# Analog-System.net
KiCad netlist of a schematic drawn in EAGLE
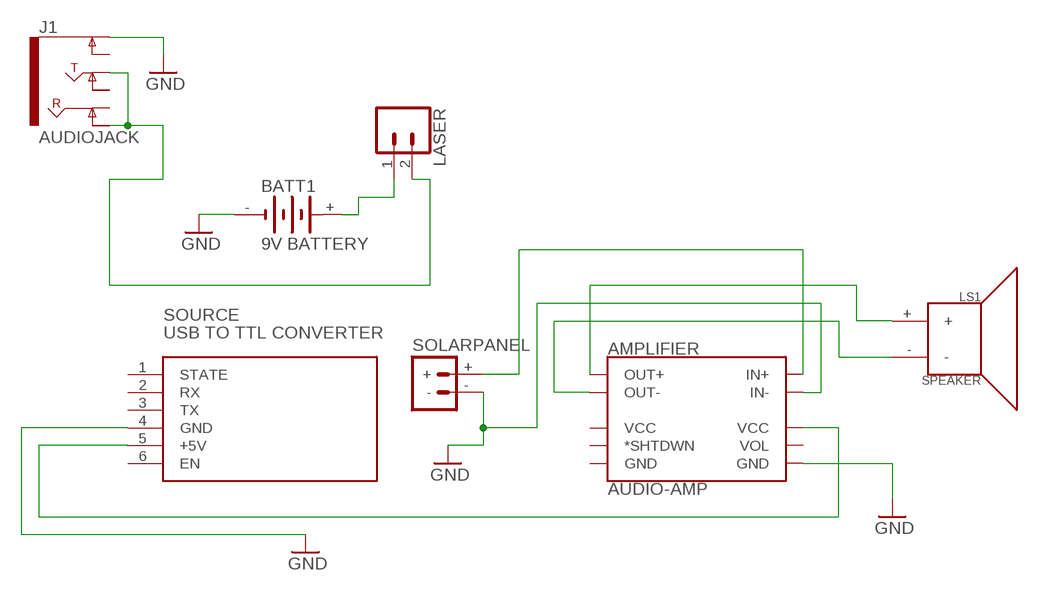
[diagram p0: schematic, sheet 1]

(export (version "E")
  (design (tool "Eeschema 10.0.6"))
  (components
    (comp (ref "AMPLIFIER")
      (value "AUDIO-AMP")
      (footprint "eagle-import:AUDIO-AMP-MONO")
      (libsource (lib "eagle-import") (part "SPARKFUN_AUDIO-AMP-MONODIP"))
    )
    (comp (ref "BATT1")
      (value "9V BATTERY")
      (footprint "eagle-import:2464BATT_HOLDER")
      (libsource (lib "eagle-import") (part "2464_BATT_HOLDER"))
    )
    (comp (ref "J1")
      (value "AUDIOJACK")
      (footprint "eagle-import:AUDIO_JACK_0.25__TRS_PTH_RA")
      (libsource (lib "eagle-import") (part "AUDIO_JACK_TRS_0.25{dblquote}_PTH_RA"))
    )
    (comp (ref "LASER")
      (value "CONN_02")
      (footprint "eagle-import:1X02")
      (libsource (lib "eagle-import") (part "CONN_02"))
    )
    (comp (ref "LS1")
      (value "SPEAKER")
      (footprint "eagle-import:PCB_MOUNT_SPEAKER")
      (libsource (lib "eagle-import") (part "SPEAKER"))
    )
    (comp (ref "SOLARPANEL")
      (value "BATTERY_CONN_DEANS")
      (footprint "eagle-import:DEANS")
      (libsource (lib "eagle-import") (part "BATTERY_CONN_DEANS"))
    )
    (comp (ref "SOURCE")
      (value "USB TO TTL CONVERTER")
      (footprint "eagle-import:WIRELESS-BLUETOOTH-HC-05")
      (libsource (lib "eagle-import") (part "WIRELESS-BLUETOOTH-HC-05"))
    )
  )
  (nets
    (net (code "1") (name "GND") (class "Default")
      (node (ref "AMPLIFIER") (pin "IN-") (pinfunction "IN-_IN-") (pintype "bidirectional"))
      (node (ref "AMPLIFIER") (pin "VOL-") (pinfunction "GND_VOL-") (pintype "bidirectional"))
      (node (ref "BATT1") (pin "-") (pinfunction "-_-") (pintype "passive"))
      (node (ref "J1") (pin "SLEEVE") (pinfunction "EARTH_SLEEVE") (pintype "bidirectional"))
      (node (ref "SOLARPANEL") (pin "-") (pinfunction "-_-") (pintype "passive"))
      (node (ref "SOURCE") (pin "4") (pinfunction "GND_4") (pintype "power_in"))
    )
    (net (code "2") (name "Net-(AMPLIFIER-PadIN+)") (class "Default")
      (node (ref "AMPLIFIER") (pin "IN+") (pinfunction "IN+_IN+") (pintype "bidirectional"))
      (node (ref "SOLARPANEL") (pin "+") (pinfunction "+_+") (pintype "passive"))
    )
    (net (code "3") (name "Net-(AMPLIFIER-PadOUT+)") (class "Default")
      (node (ref "AMPLIFIER") (pin "OUT+") (pinfunction "OUT+_OUT+") (pintype "bidirectional"))
      (node (ref "LS1") (pin "+") (pinfunction "+_+") (pintype "bidirectional"))
    )
    (net (code "4") (name "Net-(AMPLIFIER-PadOUT-)") (class "Default")
      (node (ref "AMPLIFIER") (pin "OUT-") (pinfunction "OUT-_OUT-") (pintype "bidirectional"))
      (node (ref "LS1") (pin "-") (pinfunction "-_-") (pintype "bidirectional"))
    )
    (net (code "5") (name "Net-(BATT1-Pad+)") (class "Default")
      (node (ref "BATT1") (pin "+") (pinfunction "+_+") (pintype "passive"))
      (node (ref "LASER") (pin "1") (pinfunction "1_1") (pintype "passive"))
    )
    (net (code "6") (name "Net-(J1-PadRING-NORM)") (class "Default")
      (node (ref "J1") (pin "RING-NORM") (pinfunction "RING-NORM_RING-NORM") (pintype "bidirectional"))
      (node (ref "J1") (pin "TIP") (pinfunction "TIP_TIP") (pintype "bidirectional"))
      (node (ref "LASER") (pin "2") (pinfunction "2_2") (pintype "passive"))
    )
    (net (code "7") (name "Net-(SOURCE-+5V)") (class "Default")
      (node (ref "AMPLIFIER") (pin "VOL+") (pinfunction "VCC_VOL+") (pintype "bidirectional"))
      (node (ref "SOURCE") (pin "5") (pinfunction "+5V_5") (pintype "power_in"))
    )
    (net (code "8") (name "unconnected-(AMPLIFIER-*SHTDWN-PadS)") (class "Default")
      (node (ref "AMPLIFIER") (pin "S") (pinfunction "*SHTDWN_S") (pintype "bidirectional"))
    )
    (net (code "9") (name "unconnected-(AMPLIFIER-GND-PadPWR-)") (class "Default")
      (node (ref "AMPLIFIER") (pin "PWR-") (pinfunction "GND_PWR-") (pintype "bidirectional"))
    )
    (net (code "10") (name "unconnected-(AMPLIFIER-PadVOL)") (class "Default")
      (node (ref "AMPLIFIER") (pin "VOL") (pinfunction "VOL_VOL") (pintype "bidirectional"))
    )
    (net (code "11") (name "unconnected-(AMPLIFIER-VCC-PadPWR+)") (class "Default")
      (node (ref "AMPLIFIER") (pin "PWR+") (pinfunction "VCC_PWR+") (pintype "bidirectional"))
    )
    (net (code "12") (name "unconnected-(J1-EARTH-NORM-PadSLEEVE-NORM)") (class "Default")
      (node (ref "J1") (pin "SLEEVE-NORM") (pinfunction "EARTH-NORM_SLEEVE-NORM") (pintype "bidirectional"))
    )
    (net (code "13") (name "unconnected-(J1-PadRING)") (class "Default")
      (node (ref "J1") (pin "RING") (pinfunction "RING_RING") (pintype "bidirectional"))
    )
    (net (code "14") (name "unconnected-(J1-PadTIP-NORM)") (class "Default")
      (node (ref "J1") (pin "TIP-NORM") (pinfunction "TIP-NORM_TIP-NORM") (pintype "bidirectional"))
    )
    (net (code "15") (name "unconnected-(SOURCE-EN-Pad6)") (class "Default")
      (node (ref "SOURCE") (pin "6") (pinfunction "EN_6") (pintype "bidirectional"))
    )
    (net (code "16") (name "unconnected-(SOURCE-RX-Pad2)") (class "Default")
      (node (ref "SOURCE") (pin "2") (pinfunction "RX_2") (pintype "bidirectional"))
    )
    (net (code "17") (name "unconnected-(SOURCE-STATE-Pad1)") (class "Default")
      (node (ref "SOURCE") (pin "1") (pinfunction "STATE_1") (pintype "bidirectional"))
    )
    (net (code "18") (name "unconnected-(SOURCE-TX-Pad3)") (class "Default")
      (node (ref "SOURCE") (pin "3") (pinfunction "TX_3") (pintype "bidirectional"))
    )
  )
)
